# Robotics_Cape.net
KiCad netlist of a schematic drawn in EAGLE
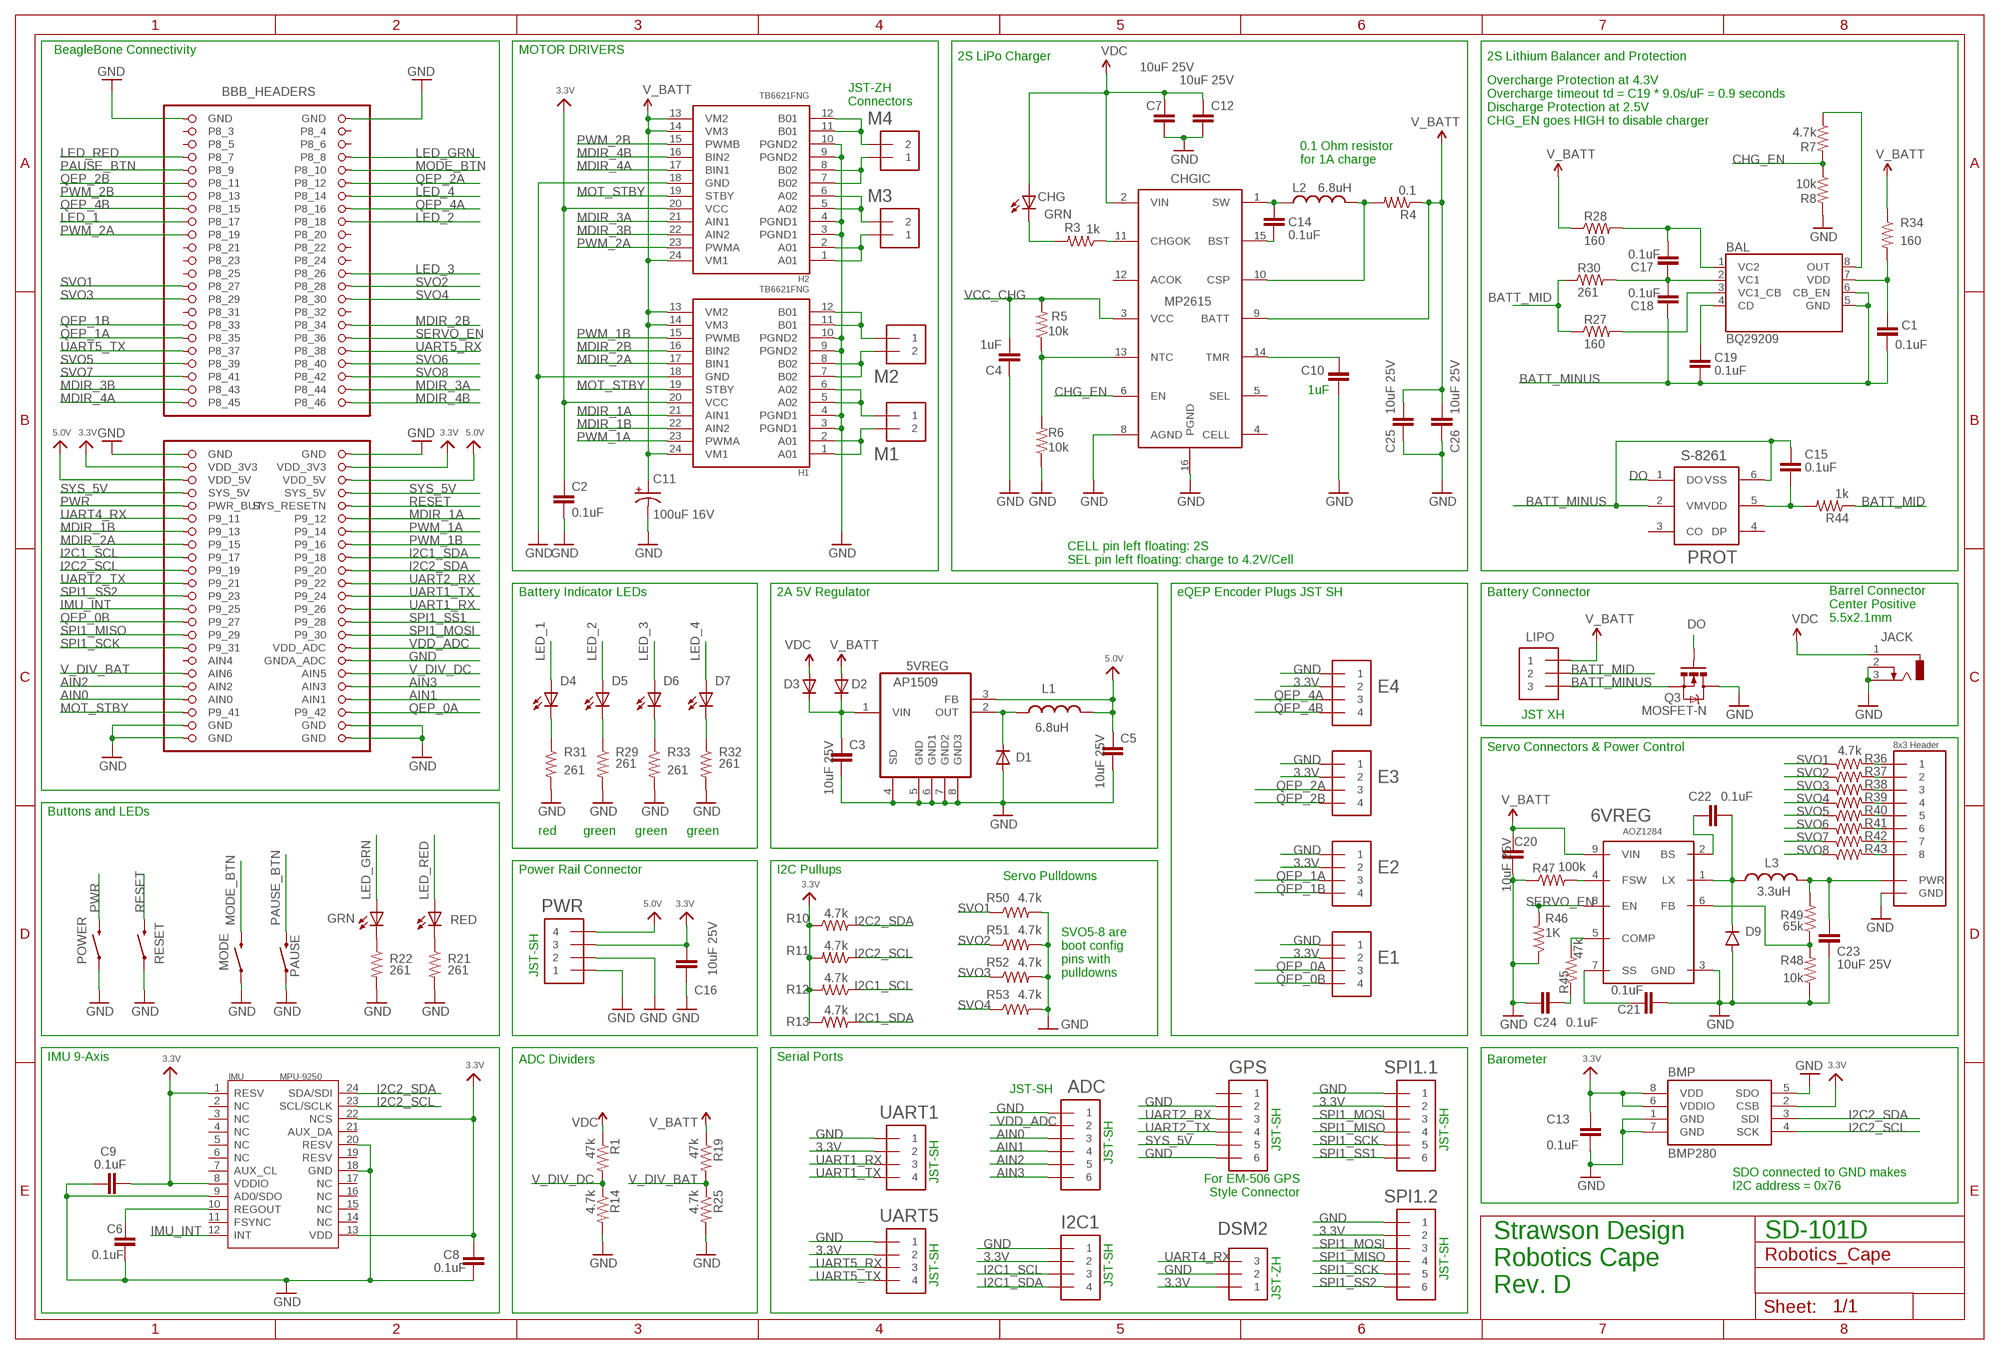
[diagram p0: schematic, sheet 1]

(export (version "E")
  (design (tool "Eeschema 10.0.6"))
  (components
    (comp (ref "5VREG")
      (value "AP1509SOIC-8-TIGHT")
      (footprint "eagle-import:SO08-TIGHT")
      (libsource (lib "eagle-import") (part "AP1509SOIC-8-TIGHT"))
    )
    (comp (ref "6VREG")
      (value "AOZ1284")
      (footprint "eagle-import:SO08-EXPOSED")
      (libsource (lib "eagle-import") (part "AOZ1284"))
    )
    (comp (ref "ADC")
      (value "JST_SH_6")
      (footprint "eagle-import:JST_SH_6")
      (libsource (lib "eagle-import") (part "JST_SH_6"))
    )
    (comp (ref "BAL")
      (value "BQ29209")
      (footprint "eagle-import:8-SON_3X3MM")
      (libsource (lib "eagle-import") (part "BQ29209"))
    )
    (comp (ref "BBB_HEADERS")
      (value "BEAGLEBONE_OUTLINE")
      (footprint "eagle-import:BEAGLEBONE_SHIELD")
      (libsource (lib "eagle-import") (part "BEAGLEBONE_OUTLINE"))
    )
    (comp (ref "BMP")
      (value "BMP280")
      (footprint "eagle-import:BMP280")
      (libsource (lib "eagle-import") (part "BMP280"))
    )
    (comp (ref "C1")
      (value "0.1uF")
      (footprint "eagle-import:0402-CAP")
      (libsource (lib "eagle-import") (part "Strawson_Eagle_Lib_CAP0402-CAP"))
    )
    (comp (ref "C2")
      (value "0.1uF")
      (footprint "eagle-import:0402-CAP")
      (libsource (lib "eagle-import") (part "Strawson_Eagle_Lib_CAP0402-CAP"))
    )
    (comp (ref "C3")
      (value "10uF 25V")
      (footprint "eagle-import:0805")
      (libsource (lib "eagle-import") (part "CAP0805"))
    )
    (comp (ref "C4")
      (value "1uF")
      (footprint "eagle-import:0402-CAP")
      (libsource (lib "eagle-import") (part "Strawson_Eagle_Lib_CAP0402-CAP"))
    )
    (comp (ref "C5")
      (value "10uF 25V")
      (footprint "eagle-import:0805")
      (libsource (lib "eagle-import") (part "CAP0805"))
    )
    (comp (ref "C6")
      (value "0.1uF")
      (footprint "eagle-import:0402-CAP")
      (libsource (lib "eagle-import") (part "Strawson_Eagle_Lib_CAP0402-CAP"))
    )
    (comp (ref "C7")
      (value "10uF 25V")
      (footprint "eagle-import:0805")
      (libsource (lib "eagle-import") (part "CAP0805"))
    )
    (comp (ref "C8")
      (value "0.1uF")
      (footprint "eagle-import:0402-CAP")
      (libsource (lib "eagle-import") (part "Strawson_Eagle_Lib_CAP0402-CAP"))
    )
    (comp (ref "C9")
      (value "0.1uF")
      (footprint "eagle-import:0402-CAP")
      (libsource (lib "eagle-import") (part "Strawson_Eagle_Lib_CAP0402-CAP"))
    )
    (comp (ref "C10")
      (value "1uF")
      (footprint "eagle-import:0402-CAP")
      (libsource (lib "eagle-import") (part "Strawson_Eagle_Lib_CAP0402-CAP"))
    )
    (comp (ref "C11")
      (value "100uF 16V")
      (footprint "eagle-import:PANASONIC_D")
      (libsource (lib "eagle-import") (part "CPOL-USD"))
    )
    (comp (ref "C12")
      (value "10uF 25V")
      (footprint "eagle-import:0805")
      (libsource (lib "eagle-import") (part "CAP0805"))
    )
    (comp (ref "C13")
      (value "0.1uF")
      (footprint "eagle-import:0402-CAP")
      (libsource (lib "eagle-import") (part "Strawson_Eagle_Lib_CAP0402-CAP"))
    )
    (comp (ref "C14")
      (value "0.1uF")
      (footprint "eagle-import:0402-CAP")
      (libsource (lib "eagle-import") (part "Strawson_Eagle_Lib_CAP0402-CAP"))
    )
    (comp (ref "C15")
      (value "0.1uF")
      (footprint "eagle-import:0402-CAP")
      (libsource (lib "eagle-import") (part "Strawson_Eagle_Lib_CAP0402-CAP"))
    )
    (comp (ref "C16")
      (value "10uF 25V")
      (footprint "eagle-import:0805")
      (libsource (lib "eagle-import") (part "CAP0805"))
    )
    (comp (ref "C17")
      (value "0.1uF")
      (footprint "eagle-import:0402-CAP")
      (libsource (lib "eagle-import") (part "Strawson_Eagle_Lib_CAP0402-CAP"))
    )
    (comp (ref "C18")
      (value "0.1uF")
      (footprint "eagle-import:0402-CAP")
      (libsource (lib "eagle-import") (part "Strawson_Eagle_Lib_CAP0402-CAP"))
    )
    (comp (ref "C19")
      (value "0.1uF")
      (footprint "eagle-import:0402-CAP")
      (libsource (lib "eagle-import") (part "Strawson_Eagle_Lib_CAP0402-CAP"))
    )
    (comp (ref "C20")
      (value "10uF 25V")
      (footprint "eagle-import:0805")
      (libsource (lib "eagle-import") (part "CAP0805"))
    )
    (comp (ref "C21")
      (value "0.1uF")
      (footprint "eagle-import:0402-CAP")
      (libsource (lib "eagle-import") (part "Strawson_Eagle_Lib_CAP0402-CAP"))
    )
    (comp (ref "C22")
      (value "0.1uF")
      (footprint "eagle-import:0402-CAP")
      (libsource (lib "eagle-import") (part "Strawson_Eagle_Lib_CAP0402-CAP"))
    )
    (comp (ref "C23")
      (value "10uF 25V")
      (footprint "eagle-import:0805")
      (libsource (lib "eagle-import") (part "CAP0805"))
    )
    (comp (ref "C24")
      (value "0.1uF")
      (footprint "eagle-import:0402-CAP")
      (libsource (lib "eagle-import") (part "Strawson_Eagle_Lib_CAP0402-CAP"))
    )
    (comp (ref "C25")
      (value "10uF 25V")
      (footprint "eagle-import:0805")
      (libsource (lib "eagle-import") (part "CAP0805"))
    )
    (comp (ref "C26")
      (value "10uF 25V")
      (footprint "eagle-import:0805")
      (libsource (lib "eagle-import") (part "CAP0805"))
    )
    (comp (ref "CHG")
      (value "GRN")
      (footprint "eagle-import:LED-0603")
      (libsource (lib "eagle-import") (part "LED0603"))
    )
    (comp (ref "CHGIC")
      (value "MP2615")
      (footprint "eagle-import:MP2615")
      (libsource (lib "eagle-import") (part "MP2615"))
    )
    (comp (ref "D1")
      (value "DIODESOD-123")
      (footprint "eagle-import:SOD-123")
      (libsource (lib "eagle-import") (part "DIODESOD-123"))
    )
    (comp (ref "D2")
      (value "DIODESOD-123")
      (footprint "eagle-import:SOD-123")
      (libsource (lib "eagle-import") (part "DIODESOD-123"))
    )
    (comp (ref "D3")
      (value "DIODESOD-123")
      (footprint "eagle-import:SOD-123")
      (libsource (lib "eagle-import") (part "DIODESOD-123"))
    )
    (comp (ref "D4")
      (value "RED")
      (footprint "eagle-import:LED-0603")
      (libsource (lib "eagle-import") (part "LED0603"))
    )
    (comp (ref "D5")
      (value "GREEN")
      (footprint "eagle-import:LED-0603")
      (libsource (lib "eagle-import") (part "LED0603"))
    )
    (comp (ref "D6")
      (value "GREEN")
      (footprint "eagle-import:LED-0603")
      (libsource (lib "eagle-import") (part "LED0603"))
    )
    (comp (ref "D7")
      (value "GREEN")
      (footprint "eagle-import:LED-0603")
      (libsource (lib "eagle-import") (part "LED0603"))
    )
    (comp (ref "D9")
      (value "DIODEDO214AA")
      (footprint "eagle-import:DO-214AA")
      (libsource (lib "eagle-import") (part "DIODEDO214AA"))
    )
    (comp (ref "DSM2")
      (value "JST_ZH_3")
      (footprint "eagle-import:JST_ZH_3")
      (libsource (lib "eagle-import") (part "JST_ZH_3"))
    )
    (comp (ref "E1")
      (value "JST_SH_4")
      (footprint "eagle-import:JST_SH_4_SMD")
      (libsource (lib "eagle-import") (part "JST_SH_4"))
    )
    (comp (ref "E2")
      (value "JST_SH_4")
      (footprint "eagle-import:JST_SH_4_SMD")
      (libsource (lib "eagle-import") (part "JST_SH_4"))
    )
    (comp (ref "E3")
      (value "JST_SH_4")
      (footprint "eagle-import:JST_SH_4_SMD")
      (libsource (lib "eagle-import") (part "JST_SH_4"))
    )
    (comp (ref "E4")
      (value "JST_SH_4")
      (footprint "eagle-import:JST_SH_4_SMD")
      (libsource (lib "eagle-import") (part "JST_SH_4"))
    )
    (comp (ref "GPS")
      (value "JST_SH_6")
      (footprint "eagle-import:JST_SH_6")
      (libsource (lib "eagle-import") (part "JST_SH_6"))
    )
    (comp (ref "GRN")
      (value "GRN")
      (footprint "eagle-import:LED-0603")
      (libsource (lib "eagle-import") (part "LED0603"))
    )
    (comp (ref "H1")
      (value "TB6621FNG")
      (footprint "eagle-import:SSOP24")
      (libsource (lib "eagle-import") (part "TB6621FNG"))
    )
    (comp (ref "H2")
      (value "TB6621FNG")
      (footprint "eagle-import:SSOP24")
      (libsource (lib "eagle-import") (part "TB6621FNG"))
    )
    (comp (ref "I2C1")
      (value "JST_SH_4")
      (footprint "eagle-import:JST_SH_4_SMD")
      (libsource (lib "eagle-import") (part "JST_SH_4"))
    )
    (comp (ref "IMU")
      (value "MPU-9250")
      (footprint "eagle-import:QFN24G-0.4-3X3MM")
      (libsource (lib "eagle-import") (part "MPU-9250"))
    )
    (comp (ref "JACK")
      (value "5.5x2.1mm")
      (footprint "eagle-import:DCJ0303")
      (libsource (lib "eagle-import") (part "DCJ0303"))
    )
    (comp (ref "L1")
      (value "6.8uH")
      (footprint "eagle-import:TAIYO_NRS")
      (libsource (lib "eagle-import") (part "INDUCTORTAIYO_NR-S"))
    )
    (comp (ref "L2")
      (value "6.8uH")
      (footprint "eagle-import:TAIYO_NRS")
      (libsource (lib "eagle-import") (part "INDUCTORTAIYO_NR-S"))
    )
    (comp (ref "L3")
      (value "3.3uH")
      (footprint "eagle-import:8X8MM_INDUCTOR")
      (libsource (lib "eagle-import") (part "INDUCTOR"))
    )
    (comp (ref "LIPO")
      (value "JST_XH_3-PIN")
      (footprint "eagle-import:JST_XH_3-PIN")
      (libsource (lib "eagle-import") (part "JST_XH_3-PIN"))
    )
    (comp (ref "M1")
      (value "JST_ZH_2")
      (footprint "eagle-import:JST_ZH_2")
      (libsource (lib "eagle-import") (part "JST_ZH_2"))
    )
    (comp (ref "M2")
      (value "JST_ZH_2")
      (footprint "eagle-import:JST_ZH_2")
      (libsource (lib "eagle-import") (part "JST_ZH_2"))
    )
    (comp (ref "M3")
      (value "JST_ZH_2")
      (footprint "eagle-import:JST_ZH_2")
      (libsource (lib "eagle-import") (part "JST_ZH_2"))
    )
    (comp (ref "M4")
      (value "JST_ZH_2")
      (footprint "eagle-import:JST_ZH_2")
      (libsource (lib "eagle-import") (part "JST_ZH_2"))
    )
    (comp (ref "MODE")
      (value "SWITCH-MOMENTARY-2-SMD-1101NE")
      (footprint "eagle-import:TACTILE-SWITCH-1101NE")
      (libsource (lib "eagle-import") (part "SWITCH-MOMENTARY-2-SMD-1101NE"))
    )
    (comp (ref "PAUSE")
      (value "SWITCH-MOMENTARY-2-SMD-1101NE")
      (footprint "eagle-import:TACTILE-SWITCH-1101NE")
      (libsource (lib "eagle-import") (part "SWITCH-MOMENTARY-2-SMD-1101NE"))
    )
    (comp (ref "POWER")
      (value "SWITCH-MOMENTARY-2-SMD-1101NE")
      (footprint "eagle-import:TACTILE-SWITCH-1101NE")
      (libsource (lib "eagle-import") (part "SWITCH-MOMENTARY-2-SMD-1101NE"))
    )
    (comp (ref "PROT")
      (value "S-8261")
      (footprint "eagle-import:SOT-236")
      (libsource (lib "eagle-import") (part "S-8261"))
    )
    (comp (ref "PWR")
      (value "JST_SH_4")
      (footprint "eagle-import:JST_SH_4_SMD")
      (libsource (lib "eagle-import") (part "JST_SH_4"))
    )
    (comp (ref "Q3")
      (value "MOSFET-N")
      (footprint "eagle-import:SO08-TIGHT")
      (libsource (lib "eagle-import") (part "MOSFET-NCHANNEL"))
    )
    (comp (ref "R1")
      (value "47k")
      (footprint "eagle-import:0402-RES")
      (libsource (lib "eagle-import") (part "RESISTOR0402-RES"))
    )
    (comp (ref "R3")
      (value "1k")
      (footprint "eagle-import:0402-RES")
      (libsource (lib "eagle-import") (part "RESISTOR0402-RES"))
    )
    (comp (ref "R4")
      (value "0.1")
      (footprint "eagle-import:0603-RES")
      (libsource (lib "eagle-import") (part "RESISTOR0603"))
    )
    (comp (ref "R5")
      (value "10k")
      (footprint "eagle-import:0402-RES")
      (libsource (lib "eagle-import") (part "RESISTOR0402-RES"))
    )
    (comp (ref "R6")
      (value "10k")
      (footprint "eagle-import:0402-RES")
      (libsource (lib "eagle-import") (part "RESISTOR0402-RES"))
    )
    (comp (ref "R7")
      (value "4.7k")
      (footprint "eagle-import:0402-RES")
      (libsource (lib "eagle-import") (part "RESISTOR0402-RES"))
    )
    (comp (ref "R8")
      (value "10k")
      (footprint "eagle-import:0402-RES")
      (libsource (lib "eagle-import") (part "RESISTOR0402-RES"))
    )
    (comp (ref "R10")
      (value "4.7k")
      (footprint "eagle-import:0402-RES")
      (libsource (lib "eagle-import") (part "RESISTOR0402-RES"))
    )
    (comp (ref "R11")
      (value "4.7k")
      (footprint "eagle-import:0402-RES")
      (libsource (lib "eagle-import") (part "RESISTOR0402-RES"))
    )
    (comp (ref "R12")
      (value "4.7k")
      (footprint "eagle-import:0402-RES")
      (libsource (lib "eagle-import") (part "RESISTOR0402-RES"))
    )
    (comp (ref "R13")
      (value "4.7k")
      (footprint "eagle-import:0402-RES")
      (libsource (lib "eagle-import") (part "RESISTOR0402-RES"))
    )
    (comp (ref "R14")
      (value "4.7k")
      (footprint "eagle-import:0402-RES")
      (libsource (lib "eagle-import") (part "RESISTOR0402-RES"))
    )
    (comp (ref "R19")
      (value "47k")
      (footprint "eagle-import:0402-RES")
      (libsource (lib "eagle-import") (part "RESISTOR0402-RES"))
    )
    (comp (ref "R21")
      (value "261")
      (footprint "eagle-import:0402-RES")
      (libsource (lib "eagle-import") (part "RESISTOR0402-RES"))
    )
    (comp (ref "R22")
      (value "261")
      (footprint "eagle-import:0402-RES")
      (libsource (lib "eagle-import") (part "RESISTOR0402-RES"))
    )
    (comp (ref "R25")
      (value "4.7k")
      (footprint "eagle-import:0402-RES")
      (libsource (lib "eagle-import") (part "RESISTOR0402-RES"))
    )
    (comp (ref "R27")
      (value "160")
      (footprint "eagle-import:0402-RES")
      (libsource (lib "eagle-import") (part "RESISTOR0402-RES"))
    )
    (comp (ref "R28")
      (value "160")
      (footprint "eagle-import:0402-RES")
      (libsource (lib "eagle-import") (part "RESISTOR0402-RES"))
    )
    (comp (ref "R29")
      (value "261")
      (footprint "eagle-import:0402-RES")
      (libsource (lib "eagle-import") (part "RESISTOR0402-RES"))
    )
    (comp (ref "R30")
      (value "261")
      (footprint "eagle-import:0402-RES")
      (libsource (lib "eagle-import") (part "RESISTOR0402-RES"))
    )
    (comp (ref "R31")
      (value "261")
      (footprint "eagle-import:0402-RES")
      (libsource (lib "eagle-import") (part "RESISTOR0402-RES"))
    )
    (comp (ref "R32")
      (value "261")
      (footprint "eagle-import:0402-RES")
      (libsource (lib "eagle-import") (part "RESISTOR0402-RES"))
    )
    (comp (ref "R33")
      (value "261")
      (footprint "eagle-import:0402-RES")
      (libsource (lib "eagle-import") (part "RESISTOR0402-RES"))
    )
    (comp (ref "R34")
      (value "160")
      (footprint "eagle-import:0402-RES")
      (libsource (lib "eagle-import") (part "RESISTOR0402-RES"))
    )
    (comp (ref "R36")
      (value "4.7k")
      (footprint "eagle-import:0402-RES")
      (libsource (lib "eagle-import") (part "RESISTOR0402-RES"))
    )
    (comp (ref "R37")
      (value "4.7k")
      (footprint "eagle-import:0402-RES")
      (libsource (lib "eagle-import") (part "RESISTOR0402-RES"))
    )
    (comp (ref "R38")
      (value "4.7k")
      (footprint "eagle-import:0402-RES")
      (libsource (lib "eagle-import") (part "RESISTOR0402-RES"))
    )
    (comp (ref "R39")
      (value "4.7k")
      (footprint "eagle-import:0402-RES")
      (libsource (lib "eagle-import") (part "RESISTOR0402-RES"))
    )
    (comp (ref "R40")
      (value "4.7k")
      (footprint "eagle-import:0402-RES")
      (libsource (lib "eagle-import") (part "RESISTOR0402-RES"))
    )
    (comp (ref "R41")
      (value "4.7k")
      (footprint "eagle-import:0402-RES")
      (libsource (lib "eagle-import") (part "RESISTOR0402-RES"))
    )
    (comp (ref "R42")
      (value "4.7k")
      (footprint "eagle-import:0402-RES")
      (libsource (lib "eagle-import") (part "RESISTOR0402-RES"))
    )
    (comp (ref "R43")
      (value "4.7k")
      (footprint "eagle-import:0402-RES")
      (libsource (lib "eagle-import") (part "RESISTOR0402-RES"))
    )
    (comp (ref "R44")
      (value "1k")
      (footprint "eagle-import:0402-RES")
      (libsource (lib "eagle-import") (part "RESISTOR0402-RES"))
    )
    (comp (ref "R45")
      (value "47k")
      (footprint "eagle-import:0402-RES")
      (libsource (lib "eagle-import") (part "RESISTOR0402-RES"))
    )
    (comp (ref "R46")
      (value "1K")
      (footprint "eagle-import:0402-RES")
      (libsource (lib "eagle-import") (part "RESISTOR0402-RES"))
    )
    (comp (ref "R47")
      (value "100k")
      (footprint "eagle-import:0402-RES")
      (libsource (lib "eagle-import") (part "RESISTOR0402-RES"))
    )
    (comp (ref "R48")
      (value "10k")
      (footprint "eagle-import:0402-RES")
      (libsource (lib "eagle-import") (part "RESISTOR0402-RES"))
    )
    (comp (ref "R49")
      (value "65k")
      (footprint "eagle-import:0402-RES")
      (libsource (lib "eagle-import") (part "RESISTOR0402-RES"))
    )
    (comp (ref "R50")
      (value "4.7k")
      (footprint "eagle-import:0402-RES")
      (libsource (lib "eagle-import") (part "RESISTOR0402-RES"))
    )
    (comp (ref "R51")
      (value "4.7k")
      (footprint "eagle-import:0402-RES")
      (libsource (lib "eagle-import") (part "RESISTOR0402-RES"))
    )
    (comp (ref "R52")
      (value "4.7k")
      (footprint "eagle-import:0402-RES")
      (libsource (lib "eagle-import") (part "RESISTOR0402-RES"))
    )
    (comp (ref "R53")
      (value "4.7k")
      (footprint "eagle-import:0402-RES")
      (libsource (lib "eagle-import") (part "RESISTOR0402-RES"))
    )
    (comp (ref "RED")
      (value "RED")
      (footprint "eagle-import:LED-0603")
      (libsource (lib "eagle-import") (part "LED0603"))
    )
    (comp (ref "RESET")
      (value "SWITCH-MOMENTARY-2-SMD-1101NE")
      (footprint "eagle-import:TACTILE-SWITCH-1101NE")
      (libsource (lib "eagle-import") (part "SWITCH-MOMENTARY-2-SMD-1101NE"))
    )
    (comp (ref "SPI1.1")
      (value "JST_SH_6")
      (footprint "eagle-import:JST_SH_6")
      (libsource (lib "eagle-import") (part "JST_SH_6"))
    )
    (comp (ref "SPI1.2")
      (value "JST_SH_6")
      (footprint "eagle-import:JST_SH_6")
      (libsource (lib "eagle-import") (part "JST_SH_6"))
    )
    (comp (ref "U$1")
      (value "SERVO_HEADERS_8X")
      (footprint "eagle-import:3X8_0.1__HEADER")
      (libsource (lib "eagle-import") (part "SERVO_HEADERS_8X"))
    )
    (comp (ref "UART1")
      (value "JST_SH_4")
      (footprint "eagle-import:JST_SH_4_SMD")
      (libsource (lib "eagle-import") (part "JST_SH_4"))
    )
    (comp (ref "UART5")
      (value "JST_SH_4")
      (footprint "eagle-import:JST_SH_4_SMD")
      (libsource (lib "eagle-import") (part "JST_SH_4"))
    )
  )
  (nets
    (net (code "1") (name "/AIN0") (class "Default")
      (node (ref "ADC") (pin "3") (pinfunction "3_3") (pintype "bidirectional"))
      (node (ref "BBB_HEADERS") (pin "85") (pinfunction "AIN0_85") (pintype "power_in"))
    )
    (net (code "2") (name "/AIN1") (class "Default")
      (node (ref "ADC") (pin "4") (pinfunction "4_4") (pintype "bidirectional"))
      (node (ref "BBB_HEADERS") (pin "86") (pinfunction "AIN1_86") (pintype "passive"))
    )
    (net (code "3") (name "/AIN2") (class "Default")
      (node (ref "ADC") (pin "5") (pinfunction "5_5") (pintype "bidirectional"))
      (node (ref "BBB_HEADERS") (pin "83") (pinfunction "AIN2_83") (pintype "passive"))
    )
    (net (code "4") (name "/AIN3") (class "Default")
      (node (ref "ADC") (pin "6") (pinfunction "6_6") (pintype "bidirectional"))
      (node (ref "BBB_HEADERS") (pin "84") (pinfunction "AIN3_84") (pintype "passive"))
    )
    (net (code "5") (name "/BATT_MID") (class "Default")
      (node (ref "LIPO") (pin "P$2") (pinfunction "2_P$2") (pintype "passive"))
      (node (ref "R27") (pin "1") (pinfunction "1_1") (pintype "passive"))
      (node (ref "R30") (pin "1") (pinfunction "1_1") (pintype "passive"))
      (node (ref "R44") (pin "1") (pinfunction "1_1") (pintype "passive"))
    )
    (net (code "6") (name "/BATT_MINUS") (class "Default")
      (node (ref "BAL") (pin "5") (pinfunction "GND_5") (pintype "bidirectional"))
      (node (ref "BAL") (pin "6") (pinfunction "CB_EN_6") (pintype "bidirectional"))
      (node (ref "C1") (pin "2") (pinfunction "2_2") (pintype "passive"))
      (node (ref "C15") (pin "1") (pinfunction "1_1") (pintype "passive"))
      (node (ref "C18") (pin "1") (pinfunction "1_1") (pintype "passive"))
      (node (ref "C19") (pin "2") (pinfunction "2_2") (pintype "passive"))
      (node (ref "LIPO") (pin "P$3") (pinfunction "3_P$3") (pintype "passive"))
      (node (ref "PROT") (pin "2") (pinfunction "VM_2") (pintype "bidirectional"))
      (node (ref "PROT") (pin "6") (pinfunction "VSS_6") (pintype "bidirectional"))
      (node (ref "Q3") (pin "1") (pinfunction "S_1") (pintype "passive"))
      (node (ref "Q3") (pin "2") (pinfunction "S_2") (pintype "passive"))
      (node (ref "Q3") (pin "3") (pinfunction "S_3") (pintype "passive"))
    )
    (net (code "7") (name "/CHG_EN") (class "Default")
      (node (ref "CHGIC") (pin "6") (pinfunction "EN_6") (pintype "bidirectional"))
      (node (ref "R7") (pin "2") (pinfunction "2_2") (pintype "passive"))
      (node (ref "R8") (pin "1") (pinfunction "1_1") (pintype "passive"))
    )
    (net (code "8") (name "/DO") (class "Default")
      (node (ref "PROT") (pin "1") (pinfunction "DO_1") (pintype "bidirectional"))
      (node (ref "Q3") (pin "4") (pinfunction "G_4") (pintype "passive"))
    )
    (net (code "9") (name "/I2C1_SCL") (class "Default")
      (node (ref "BBB_HEADERS") (pin "63") (pinfunction "P9_17_63") (pintype "passive"))
      (node (ref "I2C1") (pin "3") (pinfunction "3_3") (pintype "bidirectional"))
      (node (ref "R12") (pin "1") (pinfunction "1_1") (pintype "passive"))
    )
    (net (code "10") (name "/I2C1_SDA") (class "Default")
      (node (ref "BBB_HEADERS") (pin "64") (pinfunction "P9_18_64") (pintype "passive"))
      (node (ref "I2C1") (pin "4") (pinfunction "4_4") (pintype "bidirectional"))
      (node (ref "R13") (pin "2") (pinfunction "2_2") (pintype "passive"))
    )
    (net (code "11") (name "/I2C2_SCL") (class "Default")
      (node (ref "BBB_HEADERS") (pin "65") (pinfunction "P9_19_65") (pintype "passive"))
      (node (ref "BMP") (pin "4") (pinfunction "SCK_4") (pintype "input"))
      (node (ref "IMU") (pin "23") (pinfunction "SCL/SCLK_23") (pintype "bidirectional"))
      (node (ref "R11") (pin "1") (pinfunction "1_1") (pintype "passive"))
    )
    (net (code "12") (name "/I2C2_SDA") (class "Default")
      (node (ref "BBB_HEADERS") (pin "66") (pinfunction "P9_20_66") (pintype "passive"))
      (node (ref "BMP") (pin "3") (pinfunction "SDI_3") (pintype "bidirectional"))
      (node (ref "IMU") (pin "24") (pinfunction "SDA/SDI_24") (pintype "bidirectional"))
      (node (ref "R10") (pin "2") (pinfunction "2_2") (pintype "passive"))
    )
    (net (code "13") (name "/IMU_INT") (class "Default")
      (node (ref "BBB_HEADERS") (pin "71") (pinfunction "P9_25_71") (pintype "passive"))
      (node (ref "IMU") (pin "12") (pinfunction "INT_12") (pintype "bidirectional"))
    )
    (net (code "14") (name "/LED_1") (class "Default")
      (node (ref "BBB_HEADERS") (pin "17") (pinfunction "P8_17_17") (pintype "passive"))
      (node (ref "D4") (pin "A") (pinfunction "A_A") (pintype "passive"))
    )
    (net (code "15") (name "/LED_2") (class "Default")
      (node (ref "BBB_HEADERS") (pin "18") (pinfunction "P8_18_18") (pintype "passive"))
      (node (ref "D5") (pin "A") (pinfunction "A_A") (pintype "passive"))
    )
    (net (code "16") (name "/LED_3") (class "Default")
      (node (ref "BBB_HEADERS") (pin "26") (pinfunction "P8_26_26") (pintype "passive"))
      (node (ref "D6") (pin "A") (pinfunction "A_A") (pintype "passive"))
    )
    (net (code "17") (name "/LED_4") (class "Default")
      (node (ref "BBB_HEADERS") (pin "14") (pinfunction "P8_14_14") (pintype "passive"))
      (node (ref "D7") (pin "A") (pinfunction "A_A") (pintype "passive"))
    )
    (net (code "18") (name "/LED_GRN") (class "Default")
      (node (ref "BBB_HEADERS") (pin "8") (pinfunction "P8_8_8") (pintype "passive"))
      (node (ref "GRN") (pin "A") (pinfunction "A_A") (pintype "passive"))
    )
    (net (code "19") (name "/LED_RED") (class "Default")
      (node (ref "BBB_HEADERS") (pin "7") (pinfunction "P8_7_7") (pintype "passive"))
      (node (ref "RED") (pin "A") (pinfunction "A_A") (pintype "passive"))
    )
    (net (code "20") (name "/MDIR_1A") (class "Default")
      (node (ref "BBB_HEADERS") (pin "58") (pinfunction "P9_12_58") (pintype "passive"))
      (node (ref "H1") (pin "21") (pinfunction "AIN1_21") (pintype "bidirectional"))
    )
    (net (code "21") (name "/MDIR_1B") (class "Default")
      (node (ref "BBB_HEADERS") (pin "59") (pinfunction "P9_13_59") (pintype "passive"))
      (node (ref "H1") (pin "22") (pinfunction "AIN2_22") (pintype "bidirectional"))
    )
    (net (code "22") (name "/MDIR_2A") (class "Default")
      (node (ref "BBB_HEADERS") (pin "61") (pinfunction "P9_15_61") (pintype "passive"))
      (node (ref "H1") (pin "17") (pinfunction "BIN1_17") (pintype "bidirectional"))
    )
    (net (code "23") (name "/MDIR_2B") (class "Default")
      (node (ref "BBB_HEADERS") (pin "34") (pinfunction "P8_34_34") (pintype "passive"))
      (node (ref "H1") (pin "16") (pinfunction "BIN2_16") (pintype "bidirectional"))
    )
    (net (code "24") (name "/MDIR_3A") (class "Default")
      (node (ref "BBB_HEADERS") (pin "44") (pinfunction "P8_44_44") (pintype "passive"))
      (node (ref "H2") (pin "21") (pinfunction "AIN1_21") (pintype "bidirectional"))
    )
    (net (code "25") (name "/MDIR_3B") (class "Default")
      (node (ref "BBB_HEADERS") (pin "43") (pinfunction "P8_43_43") (pintype "passive"))
      (node (ref "H2") (pin "22") (pinfunction "AIN2_22") (pintype "bidirectional"))
    )
    (net (code "26") (name "/MDIR_4A") (class "Default")
      (node (ref "BBB_HEADERS") (pin "45") (pinfunction "P8_45_45") (pintype "passive"))
      (node (ref "H2") (pin "17") (pinfunction "BIN1_17") (pintype "bidirectional"))
    )
    (net (code "27") (name "/MDIR_4B") (class "Default")
      (node (ref "BBB_HEADERS") (pin "46") (pinfunction "P8_46_46") (pintype "passive"))
      (node (ref "H2") (pin "16") (pinfunction "BIN2_16") (pintype "bidirectional"))
    )
    (net (code "28") (name "/MODE_BTN") (class "Default")
      (node (ref "BBB_HEADERS") (pin "10") (pinfunction "P8_10_10") (pintype "passive"))
      (node (ref "MODE") (pin "P$2") (pinfunction "2_P$2") (pintype "passive"))
    )
    (net (code "29") (name "/MOT_STBY") (class "Default")
      (node (ref "BBB_HEADERS") (pin "87") (pinfunction "P9_41_87") (pintype "input"))
      (node (ref "H1") (pin "19") (pinfunction "STBY_19") (pintype "bidirectional"))
      (node (ref "H2") (pin "19") (pinfunction "STBY_19") (pintype "bidirectional"))
    )
    (net (code "30") (name "/PAUSE_BTN") (class "Default")
      (node (ref "BBB_HEADERS") (pin "9") (pinfunction "P8_9_9") (pintype "passive"))
      (node (ref "PAUSE") (pin "P$2") (pinfunction "2_P$2") (pintype "passive"))
    )
    (net (code "31") (name "/PWM_1A") (class "Default")
      (node (ref "BBB_HEADERS") (pin "60") (pinfunction "P9_14_60") (pintype "passive"))
      (node (ref "H1") (pin "23") (pinfunction "PWMA_23") (pintype "bidirectional"))
    )
    (net (code "32") (name "/PWM_1B") (class "Default")
      (node (ref "BBB_HEADERS") (pin "62") (pinfunction "P9_16_62") (pintype "passive"))
      (node (ref "H1") (pin "15") (pinfunction "PWMB_15") (pintype "bidirectional"))
    )
    (net (code "33") (name "/PWM_2A") (class "Default")
      (node (ref "BBB_HEADERS") (pin "19") (pinfunction "P8_19_19") (pintype "passive"))
      (node (ref "H2") (pin "23") (pinfunction "PWMA_23") (pintype "bidirectional"))
    )
    (net (code "34") (name "/PWM_2B") (class "Default")
      (node (ref "BBB_HEADERS") (pin "13") (pinfunction "P8_13_13") (pintype "passive"))
      (node (ref "H2") (pin "15") (pinfunction "PWMB_15") (pintype "bidirectional"))
    )
    (net (code "35") (name "/PWR") (class "Default")
      (node (ref "BBB_HEADERS") (pin "55") (pinfunction "PWR_BUT_55") (pintype "passive"))
      (node (ref "POWER") (pin "P$2") (pinfunction "2_P$2") (pintype "passive"))
    )
    (net (code "36") (name "/QEP_0A") (class "Default")
      (node (ref "BBB_HEADERS") (pin "88") (pinfunction "P9_42_88") (pintype "passive"))
      (node (ref "E1") (pin "3") (pinfunction "3_3") (pintype "bidirectional"))
    )
    (net (code "37") (name "/QEP_0B") (class "Default")
      (node (ref "BBB_HEADERS") (pin "73") (pinfunction "P9_27_73") (pintype "passive"))
      (node (ref "E1") (pin "4") (pinfunction "4_4") (pintype "bidirectional"))
    )
    (net (code "38") (name "/QEP_1A") (class "Default")
      (node (ref "BBB_HEADERS") (pin "35") (pinfunction "P8_35_35") (pintype "passive"))
      (node (ref "E2") (pin "3") (pinfunction "3_3") (pintype "bidirectional"))
    )
    (net (code "39") (name "/QEP_1B") (class "Default")
      (node (ref "BBB_HEADERS") (pin "33") (pinfunction "P8_33_33") (pintype "passive"))
      (node (ref "E2") (pin "4") (pinfunction "4_4") (pintype "bidirectional"))
    )
    (net (code "40") (name "/QEP_2A") (class "Default")
      (node (ref "BBB_HEADERS") (pin "12") (pinfunction "P8_12_12") (pintype "passive"))
      (node (ref "E3") (pin "3") (pinfunction "3_3") (pintype "bidirectional"))
    )
    (net (code "41") (name "/QEP_2B") (class "Default")
      (node (ref "BBB_HEADERS") (pin "11") (pinfunction "P8_11_11") (pintype "passive"))
      (node (ref "E3") (pin "4") (pinfunction "4_4") (pintype "bidirectional"))
    )
    (net (code "42") (name "/QEP_4A") (class "Default")
      (node (ref "BBB_HEADERS") (pin "16") (pinfunction "P8_16_16") (pintype "passive"))
      (node (ref "E4") (pin "3") (pinfunction "3_3") (pintype "bidirectional"))
    )
    (net (code "43") (name "/QEP_4B") (class "Default")
      (node (ref "BBB_HEADERS") (pin "15") (pinfunction "P8_15_15") (pintype "passive"))
      (node (ref "E4") (pin "4") (pinfunction "4_4") (pintype "bidirectional"))
    )
    (net (code "44") (name "/RESET") (class "Default")
      (node (ref "BBB_HEADERS") (pin "56") (pinfunction "SYS_RESETN_56") (pintype "passive"))
      (node (ref "RESET") (pin "P$2") (pinfunction "2_P$2") (pintype "passive"))
    )
    (net (code "45") (name "/SERVO_EN") (class "Default")
      (node (ref "6VREG") (pin "8") (pinfunction "EN_8") (pintype "bidirectional"))
      (node (ref "BBB_HEADERS") (pin "36") (pinfunction "P8_36_36") (pintype "passive"))
      (node (ref "R46") (pin "2") (pinfunction "2_2") (pintype "passive"))
    )
    (net (code "46") (name "/SPI1_MISO") (class "Default")
      (node (ref "BBB_HEADERS") (pin "75") (pinfunction "P9_29_75") (pintype "passive"))
      (node (ref "SPI1.1") (pin "4") (pinfunction "4_4") (pintype "bidirectional"))
      (node (ref "SPI1.2") (pin "4") (pinfunction "4_4") (pintype "bidirectional"))
    )
    (net (code "47") (name "/SPI1_MOSI") (class "Default")
      (node (ref "BBB_HEADERS") (pin "76") (pinfunction "P9_30_76") (pintype "passive"))
      (node (ref "SPI1.1") (pin "3") (pinfunction "3_3") (pintype "bidirectional"))
      (node (ref "SPI1.2") (pin "3") (pinfunction "3_3") (pintype "bidirectional"))
    )
    (net (code "48") (name "/SPI1_SCK") (class "Default")
      (node (ref "BBB_HEADERS") (pin "77") (pinfunction "P9_31_77") (pintype "passive"))
      (node (ref "SPI1.1") (pin "5") (pinfunction "5_5") (pintype "bidirectional"))
      (node (ref "SPI1.2") (pin "5") (pinfunction "5_5") (pintype "bidirectional"))
    )
    (net (code "49") (name "/SPI1_SS1") (class "Default")
      (node (ref "BBB_HEADERS") (pin "74") (pinfunction "P9_28_74") (pintype "passive"))
      (node (ref "SPI1.1") (pin "6") (pinfunction "6_6") (pintype "bidirectional"))
    )
    (net (code "50") (name "/SPI1_SS2") (class "Default")
      (node (ref "BBB_HEADERS") (pin "69") (pinfunction "P9_23_69") (pintype "passive"))
      (node (ref "SPI1.2") (pin "6") (pinfunction "6_6") (pintype "bidirectional"))
    )
    (net (code "51") (name "/SVO1") (class "Default")
      (node (ref "BBB_HEADERS") (pin "27") (pinfunction "P8_27_27") (pintype "passive"))
      (node (ref "R36") (pin "1") (pinfunction "1_1") (pintype "passive"))
      (node (ref "R50") (pin "1") (pinfunction "1_1") (pintype "passive"))
    )
    (net (code "52") (name "/SVO2") (class "Default")
      (node (ref "BBB_HEADERS") (pin "28") (pinfunction "P8_28_28") (pintype "passive"))
      (node (ref "R37") (pin "1") (pinfunction "1_1") (pintype "passive"))
      (node (ref "R51") (pin "1") (pinfunction "1_1") (pintype "passive"))
    )
    (net (code "53") (name "/SVO3") (class "Default")
      (node (ref "BBB_HEADERS") (pin "29") (pinfunction "P8_29_29") (pintype "passive"))
      (node (ref "R38") (pin "1") (pinfunction "1_1") (pintype "passive"))
      (node (ref "R52") (pin "1") (pinfunction "1_1") (pintype "passive"))
    )
    (net (code "54") (name "/SVO4") (class "Default")
      (node (ref "BBB_HEADERS") (pin "30") (pinfunction "P8_30_30") (pintype "passive"))
      (node (ref "R39") (pin "1") (pinfunction "1_1") (pintype "passive"))
      (node (ref "R53") (pin "1") (pinfunction "1_1") (pintype "passive"))
    )
    (net (code "55") (name "/SVO5") (class "Default")
      (node (ref "BBB_HEADERS") (pin "39") (pinfunction "P8_39_39") (pintype "passive"))
      (node (ref "R40") (pin "1") (pinfunction "1_1") (pintype "passive"))
    )
    (net (code "56") (name "/SVO6") (class "Default")
      (node (ref "BBB_HEADERS") (pin "40") (pinfunction "P8_40_40") (pintype "passive"))
      (node (ref "R41") (pin "1") (pinfunction "1_1") (pintype "passive"))
    )
    (net (code "57") (name "/SVO7") (class "Default")
      (node (ref "BBB_HEADERS") (pin "41") (pinfunction "P8_41_41") (pintype "passive"))
      (node (ref "R42") (pin "1") (pinfunction "1_1") (pintype "passive"))
    )
    (net (code "58") (name "/SVO8") (class "Default")
      (node (ref "BBB_HEADERS") (pin "42") (pinfunction "P8_42_42") (pintype "passive"))
      (node (ref "R43") (pin "1") (pinfunction "1_1") (pintype "passive"))
    )
    (net (code "59") (name "/SYS_5V") (class "Default")
      (node (ref "BBB_HEADERS") (pin "53") (pinfunction "SYS_5V_53") (pintype "power_in"))
      (node (ref "BBB_HEADERS") (pin "54") (pinfunction "SYS_5V_54") (pintype "passive"))
      (node (ref "GPS") (pin "5") (pinfunction "5_5") (pintype "bidirectional"))
    )
    (net (code "60") (name "/UART1_RX") (class "Default")
      (node (ref "BBB_HEADERS") (pin "72") (pinfunction "P9_26_72") (pintype "passive"))
      (node (ref "UART1") (pin "3") (pinfunction "3_3") (pintype "bidirectional"))
    )
    (net (code "61") (name "/UART1_TX") (class "Default")
      (node (ref "BBB_HEADERS") (pin "70") (pinfunction "P9_24_70") (pintype "passive"))
      (node (ref "UART1") (pin "4") (pinfunction "4_4") (pintype "bidirectional"))
    )
    (net (code "62") (name "/UART2_RX") (class "Default")
      (node (ref "BBB_HEADERS") (pin "68") (pinfunction "P9_22_68") (pintype "passive"))
      (node (ref "GPS") (pin "3") (pinfunction "3_3") (pintype "bidirectional"))
    )
    (net (code "63") (name "/UART2_TX") (class "Default")
      (node (ref "BBB_HEADERS") (pin "67") (pinfunction "P9_21_67") (pintype "passive"))
      (node (ref "GPS") (pin "4") (pinfunction "4_4") (pintype "bidirectional"))
    )
    (net (code "64") (name "/UART4_RX") (class "Default")
      (node (ref "BBB_HEADERS") (pin "57") (pinfunction "P9_11_57") (pintype "passive"))
      (node (ref "DSM2") (pin "P$3") (pinfunction "3_P$3") (pintype "bidirectional"))
    )
    (net (code "65") (name "/UART5_RX") (class "Default")
      (node (ref "BBB_HEADERS") (pin "38") (pinfunction "P8_38_38") (pintype "passive"))
      (node (ref "UART5") (pin "3") (pinfunction "3_3") (pintype "bidirectional"))
    )
    (net (code "66") (name "/UART5_TX") (class "Default")
      (node (ref "BBB_HEADERS") (pin "37") (pinfunction "P8_37_37") (pintype "passive"))
      (node (ref "UART5") (pin "4") (pinfunction "4_4") (pintype "bidirectional"))
    )
    (net (code "67") (name "/VCC_CHG") (class "Default")
      (node (ref "C4") (pin "2") (pinfunction "2_2") (pintype "passive"))
      (node (ref "CHGIC") (pin "3") (pinfunction "VCC_3") (pintype "bidirectional"))
      (node (ref "R5") (pin "2") (pinfunction "2_2") (pintype "passive"))
    )
    (net (code "68") (name "/VDD_ADC") (class "Default")
      (node (ref "ADC") (pin "2") (pinfunction "2_2") (pintype "bidirectional"))
      (node (ref "BBB_HEADERS") (pin "78") (pinfunction "VDD_ADC_78") (pintype "passive"))
    )
    (net (code "69") (name "/V_DIV_BAT") (class "Default")
      (node (ref "BBB_HEADERS") (pin "81") (pinfunction "AIN6_81") (pintype "passive"))
      (node (ref "R19") (pin "2") (pinfunction "2_2") (pintype "passive"))
      (node (ref "R25") (pin "1") (pinfunction "1_1") (pintype "passive"))
    )
    (net (code "70") (name "/V_DIV_DC") (class "Default")
      (node (ref "BBB_HEADERS") (pin "82") (pinfunction "AIN5_82") (pintype "passive"))
      (node (ref "R1") (pin "2") (pinfunction "2_2") (pintype "passive"))
      (node (ref "R14") (pin "1") (pinfunction "1_1") (pintype "passive"))
    )
    (net (code "71") (name "3.3V") (class "Default")
      (node (ref "BBB_HEADERS") (pin "49") (pinfunction "VDD_3V3_49") (pintype "power_in"))
      (node (ref "BBB_HEADERS") (pin "50") (pinfunction "VDD_3V3_50") (pintype "power_in"))
      (node (ref "BMP") (pin "2") (pinfunction "CSB_2") (pintype "input"))
      (node (ref "BMP") (pin "6") (pinfunction "VDDIO_6") (pintype "input"))
      (node (ref "BMP") (pin "8") (pinfunction "VDD_8") (pintype "power_in"))
      (node (ref "C13") (pin "1") (pinfunction "1_1") (pintype "passive"))
      (node (ref "C16") (pin "1") (pinfunction "1_1") (pintype "passive"))
      (node (ref "C2") (pin "2") (pinfunction "2_2") (pintype "passive"))
      (node (ref "C8") (pin "1") (pinfunction "1_1") (pintype "passive"))
      (node (ref "C9") (pin "2") (pinfunction "2_2") (pintype "passive"))
      (node (ref "DSM2") (pin "P$1") (pinfunction "1_P$1") (pintype "bidirectional"))
      (node (ref "E1") (pin "2") (pinfunction "2_2") (pintype "bidirectional"))
      (node (ref "E2") (pin "2") (pinfunction "2_2") (pintype "bidirectional"))
      (node (ref "E3") (pin "2") (pinfunction "2_2") (pintype "bidirectional"))
      (node (ref "E4") (pin "2") (pinfunction "2_2") (pintype "bidirectional"))
      (node (ref "H1") (pin "20") (pinfunction "VCC_20") (pintype "bidirectional"))
      (node (ref "H2") (pin "20") (pinfunction "VCC_20") (pintype "bidirectional"))
      (node (ref "I2C1") (pin "2") (pinfunction "2_2") (pintype "bidirectional"))
      (node (ref "IMU") (pin "1") (pinfunction "RESV_1") (pintype "bidirectional"))
      (node (ref "IMU") (pin "13") (pinfunction "VDD_13") (pintype "bidirectional"))
      (node (ref "IMU") (pin "22") (pinfunction "NCS_22") (pintype "bidirectional"))
      (node (ref "IMU") (pin "8") (pinfunction "VDDIO_8") (pintype "bidirectional"))
      (node (ref "PWR") (pin "3") (pinfunction "3_3") (pintype "bidirectional"))
      (node (ref "R10") (pin "1") (pinfunction "1_1") (pintype "passive"))
      (node (ref "R11") (pin "2") (pinfunction "2_2") (pintype "passive"))
      (node (ref "R12") (pin "2") (pinfunction "2_2") (pintype "passive"))
      (node (ref "R13") (pin "1") (pinfunction "1_1") (pintype "passive"))
      (node (ref "SPI1.1") (pin "2") (pinfunction "2_2") (pintype "bidirectional"))
      (node (ref "SPI1.2") (pin "2") (pinfunction "2_2") (pintype "bidirectional"))
      (node (ref "UART1") (pin "2") (pinfunction "2_2") (pintype "bidirectional"))
      (node (ref "UART5") (pin "2") (pinfunction "2_2") (pintype "bidirectional"))
    )
    (net (code "72") (name "5.0V") (class "Default")
      (node (ref "5VREG") (pin "3") (pinfunction "FB_3") (pintype "output"))
      (node (ref "BBB_HEADERS") (pin "51") (pinfunction "VDD_5V_51") (pintype "power_in"))
      (node (ref "BBB_HEADERS") (pin "52") (pinfunction "VDD_5V_52") (pintype "power_in"))
      (node (ref "C5") (pin "1") (pinfunction "1_1") (pintype "passive"))
      (node (ref "L1") (pin "2") (pinfunction "2_2") (pintype "passive"))
      (node (ref "PWR") (pin "4") (pinfunction "4_4") (pintype "bidirectional"))
    )
    (net (code "73") (name "GND") (class "Default")
      (node (ref "5VREG") (pin "4") (pinfunction "SD_4") (pintype "input"))
      (node (ref "5VREG") (pin "5") (pinfunction "GND_5") (pintype "power_in"))
      (node (ref "5VREG") (pin "6") (pinfunction "GND1_6") (pintype "input"))
      (node (ref "5VREG") (pin "7") (pinfunction "GND2_7") (pintype "passive"))
      (node (ref "5VREG") (pin "8") (pinfunction "GND3_8") (pintype "power_in"))
      (node (ref "6VREG") (pin "3") (pinfunction "GND_3") (pintype "bidirectional"))
      (node (ref "ADC") (pin "1") (pinfunction "1_1") (pintype "bidirectional"))
      (node (ref "BBB_HEADERS") (pin "1") (pinfunction "GND_1") (pintype "power_in"))
      (node (ref "BBB_HEADERS") (pin "2") (pinfunction "GND_2") (pintype "power_in"))
      (node (ref "BBB_HEADERS") (pin "47") (pinfunction "GND_47") (pintype "power_in"))
      (node (ref "BBB_HEADERS") (pin "48") (pinfunction "GND_48") (pintype "power_in"))
      (node (ref "BBB_HEADERS") (pin "80") (pinfunction "GNDA_ADC_80") (pintype "passive"))
      (node (ref "BBB_HEADERS") (pin "89") (pinfunction "GND_89") (pintype "power_in"))
      (node (ref "BBB_HEADERS") (pin "90") (pinfunction "GND_90") (pintype "power_in"))
      (node (ref "BBB_HEADERS") (pin "91") (pinfunction "GND_91") (pintype "power_in"))
      (node (ref "BBB_HEADERS") (pin "92") (pinfunction "GND_92") (pintype "power_in"))
      (node (ref "BMP") (pin "1") (pinfunction "GND_1") (pintype "power_in"))
      (node (ref "BMP") (pin "5") (pinfunction "SDO_5") (pintype "bidirectional"))
      (node (ref "BMP") (pin "7") (pinfunction "GND_7") (pintype "power_in"))
      (node (ref "C10") (pin "1") (pinfunction "1_1") (pintype "passive"))
      (node (ref "C11") (pin "-") (pinfunction "-_-") (pintype "passive"))
      (node (ref "C12") (pin "2") (pinfunction "2_2") (pintype "passive"))
      (node (ref "C13") (pin "2") (pinfunction "2_2") (pintype "passive"))
      (node (ref "C16") (pin "2") (pinfunction "2_2") (pintype "passive"))
      (node (ref "C2") (pin "1") (pinfunction "1_1") (pintype "passive"))
      (node (ref "C20") (pin "1") (pinfunction "1_1") (pintype "passive"))
      (node (ref "C21") (pin "1") (pinfunction "1_1") (pintype "passive"))
      (node (ref "C23") (pin "1") (pinfunction "1_1") (pintype "passive"))
      (node (ref "C24") (pin "1") (pinfunction "1_1") (pintype "passive"))
      (node (ref "C25") (pin "2") (pinfunction "2_2") (pintype "passive"))
      (node (ref "C26") (pin "2") (pinfunction "2_2") (pintype "passive"))
      (node (ref "C3") (pin "2") (pinfunction "2_2") (pintype "passive"))
      (node (ref "C4") (pin "1") (pinfunction "1_1") (pintype "passive"))
      (node (ref "C5") (pin "2") (pinfunction "2_2") (pintype "passive"))
      (node (ref "C6") (pin "2") (pinfunction "2_2") (pintype "passive"))
      (node (ref "C7") (pin "2") (pinfunction "2_2") (pintype "passive"))
      (node (ref "C8") (pin "2") (pinfunction "2_2") (pintype "passive"))
      (node (ref "C9") (pin "1") (pinfunction "1_1") (pintype "passive"))
      (node (ref "CHGIC") (pin "16") (pinfunction "PGND_16") (pintype "bidirectional"))
      (node (ref "CHGIC") (pin "8") (pinfunction "AGND_8") (pintype "bidirectional"))
      (node (ref "D1") (pin "A") (pinfunction "A_A") (pintype "passive"))
      (node (ref "D9") (pin "A") (pinfunction "A_A") (pintype "passive"))
      (node (ref "DSM2") (pin "P$2") (pinfunction "2_P$2") (pintype "bidirectional"))
      (node (ref "E1") (pin "1") (pinfunction "1_1") (pintype "bidirectional"))
      (node (ref "E2") (pin "1") (pinfunction "1_1") (pintype "bidirectional"))
      (node (ref "E3") (pin "1") (pinfunction "1_1") (pintype "bidirectional"))
      (node (ref "E4") (pin "1") (pinfunction "1_1") (pintype "bidirectional"))
      (node (ref "GPS") (pin "2") (pinfunction "2_2") (pintype "bidirectional"))
      (node (ref "GPS") (pin "6") (pinfunction "6_6") (pintype "bidirectional"))
      (node (ref "H1") (pin "10") (pinfunction "PGND2_10") (pintype "bidirectional"))
      (node (ref "H1") (pin "18") (pinfunction "GND_18") (pintype "bidirectional"))
      (node (ref "H1") (pin "3") (pinfunction "PGND1_3") (pintype "bidirectional"))
      (node (ref "H1") (pin "4") (pinfunction "PGND1_4") (pintype "bidirectional"))
      (node (ref "H1") (pin "9") (pinfunction "PGND2_9") (pintype "bidirectional"))
      (node (ref "H2") (pin "10") (pinfunction "PGND2_10") (pintype "bidirectional"))
      (node (ref "H2") (pin "18") (pinfunction "GND_18") (pintype "bidirectional"))
      (node (ref "H2") (pin "3") (pinfunction "PGND1_3") (pintype "bidirectional"))
      (node (ref "H2") (pin "4") (pinfunction "PGND1_4") (pintype "bidirectional"))
      (node (ref "H2") (pin "9") (pinfunction "PGND2_9") (pintype "bidirectional"))
      (node (ref "I2C1") (pin "1") (pinfunction "1_1") (pintype "bidirectional"))
      (node (ref "IMU") (pin "18") (pinfunction "GND_18") (pintype "bidirectional"))
      (node (ref "IMU") (pin "20") (pinfunction "RESV_20") (pintype "bidirectional"))
      (node (ref "IMU") (pin "9") (pinfunction "AD0/SDO_9") (pintype "bidirectional"))
      (node (ref "JACK") (pin "2") (pinfunction "2_2") (pintype "passive"))
      (node (ref "JACK") (pin "3") (pinfunction "3_3") (pintype "passive"))
      (node (ref "MODE") (pin "P$1") (pinfunction "1_P$1") (pintype "passive"))
      (node (ref "PAUSE") (pin "P$1") (pinfunction "1_P$1") (pintype "passive"))
      (node (ref "POWER") (pin "P$1") (pinfunction "1_P$1") (pintype "passive"))
      (node (ref "PWR") (pin "1") (pinfunction "1_1") (pintype "bidirectional"))
      (node (ref "PWR") (pin "2") (pinfunction "2_2") (pintype "bidirectional"))
      (node (ref "Q3") (pin "5") (pinfunction "D_5") (pintype "passive"))
      (node (ref "Q3") (pin "6") (pinfunction "D_6") (pintype "passive"))
      (node (ref "Q3") (pin "7") (pinfunction "D_7") (pintype "passive"))
      (node (ref "Q3") (pin "8") (pinfunction "D_8") (pintype "passive"))
      (node (ref "R14") (pin "2") (pinfunction "2_2") (pintype "passive"))
      (node (ref "R21") (pin "2") (pinfunction "2_2") (pintype "passive"))
      (node (ref "R22") (pin "2") (pinfunction "2_2") (pintype "passive"))
      (node (ref "R25") (pin "2") (pinfunction "2_2") (pintype "passive"))
      (node (ref "R29") (pin "2") (pinfunction "2_2") (pintype "passive"))
      (node (ref "R31") (pin "2") (pinfunction "2_2") (pintype "passive"))
      (node (ref "R32") (pin "2") (pinfunction "2_2") (pintype "passive"))
      (node (ref "R33") (pin "2") (pinfunction "2_2") (pintype "passive"))
      (node (ref "R46") (pin "1") (pinfunction "1_1") (pintype "passive"))
      (node (ref "R47") (pin "1") (pinfunction "1_1") (pintype "passive"))
      (node (ref "R48") (pin "1") (pinfunction "1_1") (pintype "passive"))
      (node (ref "R50") (pin "2") (pinfunction "2_2") (pintype "passive"))
      (node (ref "R51") (pin "2") (pinfunction "2_2") (pintype "passive"))
      (node (ref "R52") (pin "2") (pinfunction "2_2") (pintype "passive"))
      (node (ref "R53") (pin "2") (pinfunction "2_2") (pintype "passive"))
      (node (ref "R6") (pin "1") (pinfunction "1_1") (pintype "passive"))
      (node (ref "R8") (pin "2") (pinfunction "2_2") (pintype "passive"))
      (node (ref "RESET") (pin "P$1") (pinfunction "1_P$1") (pintype "passive"))
      (node (ref "SPI1.1") (pin "1") (pinfunction "1_1") (pintype "bidirectional"))
      (node (ref "SPI1.2") (pin "1") (pinfunction "1_1") (pintype "bidirectional"))
      (node (ref "U$1") (pin "P$13") (pinfunction "GND_P$13") (pintype "bidirectional"))
      (node (ref "U$1") (pin "P$14") (pinfunction "GND_P$14") (pintype "bidirectional"))
      (node (ref "U$1") (pin "P$15") (pinfunction "GND_P$15") (pintype "bidirectional"))
      (node (ref "U$1") (pin "P$16") (pinfunction "GND_P$16") (pintype "bidirectional"))
      (node (ref "U$1") (pin "P$17") (pinfunction "GND_P$17") (pintype "bidirectional"))
      (node (ref "U$1") (pin "P$18") (pinfunction "GND_P$18") (pintype "bidirectional"))
      (node (ref "U$1") (pin "P$23") (pinfunction "GND_P$23") (pintype "bidirectional"))
      (node (ref "U$1") (pin "P$24") (pinfunction "GND_P$24") (pintype "bidirectional"))
      (node (ref "UART1") (pin "1") (pinfunction "1_1") (pintype "bidirectional"))
      (node (ref "UART5") (pin "1") (pinfunction "1_1") (pintype "bidirectional"))
    )
    (net (code "74") (name "Net-(5VREG-OUT)") (class "Default")
      (node (ref "5VREG") (pin "2") (pinfunction "OUT_2") (pintype "output"))
      (node (ref "D1") (pin "C") (pinfunction "C_C") (pintype "passive"))
      (node (ref "L1") (pin "1") (pinfunction "1_1") (pintype "passive"))
    )
    (net (code "75") (name "Net-(5VREG-VIN)") (class "Default")
      (node (ref "5VREG") (pin "1") (pinfunction "VIN_1") (pintype "input"))
      (node (ref "C3") (pin "1") (pinfunction "1_1") (pintype "passive"))
      (node (ref "D2") (pin "C") (pinfunction "C_C") (pintype "passive"))
      (node (ref "D3") (pin "C") (pinfunction "C_C") (pintype "passive"))
    )
    (net (code "76") (name "Net-(6VREG-BS)") (class "Default")
      (node (ref "6VREG") (pin "2") (pinfunction "BS_2") (pintype "bidirectional"))
      (node (ref "C22") (pin "1") (pinfunction "1_1") (pintype "passive"))
    )
    (net (code "77") (name "Net-(6VREG-COMP)") (class "Default")
      (node (ref "6VREG") (pin "5") (pinfunction "COMP_5") (pintype "bidirectional"))
      (node (ref "R45") (pin "2") (pinfunction "2_2") (pintype "passive"))
    )
    (net (code "78") (name "Net-(6VREG-FB)") (class "Default")
      (node (ref "6VREG") (pin "6") (pinfunction "FB_6") (pintype "bidirectional"))
      (node (ref "R48") (pin "2") (pinfunction "2_2") (pintype "passive"))
      (node (ref "R49") (pin "1") (pinfunction "1_1") (pintype "passive"))
    )
    (net (code "79") (name "Net-(6VREG-FSW)") (class "Default")
      (node (ref "6VREG") (pin "4") (pinfunction "FSW_4") (pintype "bidirectional"))
      (node (ref "R47") (pin "2") (pinfunction "2_2") (pintype "passive"))
    )
    (net (code "80") (name "Net-(6VREG-LX)") (class "Default")
      (node (ref "6VREG") (pin "1") (pinfunction "LX_1") (pintype "bidirectional"))
      (node (ref "C22") (pin "2") (pinfunction "2_2") (pintype "passive"))
      (node (ref "D9") (pin "C") (pinfunction "C_C") (pintype "passive"))
      (node (ref "L3") (pin "1") (pinfunction "1_1") (pintype "passive"))
    )
    (net (code "81") (name "Net-(6VREG-SS)") (class "Default")
      (node (ref "6VREG") (pin "7") (pinfunction "SS_7") (pintype "bidirectional"))
      (node (ref "C21") (pin "2") (pinfunction "2_2") (pintype "passive"))
    )
    (net (code "82") (name "Net-(BAL-CD)") (class "Default")
      (node (ref "BAL") (pin "4") (pinfunction "CD_4") (pintype "bidirectional"))
      (node (ref "C19") (pin "1") (pinfunction "1_1") (pintype "passive"))
    )
    (net (code "83") (name "Net-(BAL-OUT)") (class "Default")
      (node (ref "BAL") (pin "8") (pinfunction "OUT_8") (pintype "bidirectional"))
      (node (ref "R7") (pin "1") (pinfunction "1_1") (pintype "passive"))
    )
    (net (code "84") (name "Net-(BAL-VC1)") (class "Default")
      (node (ref "BAL") (pin "2") (pinfunction "VC1_2") (pintype "bidirectional"))
      (node (ref "C17") (pin "1") (pinfunction "1_1") (pintype "passive"))
      (node (ref "C18") (pin "2") (pinfunction "2_2") (pintype "passive"))
      (node (ref "R30") (pin "2") (pinfunction "2_2") (pintype "passive"))
    )
    (net (code "85") (name "Net-(BAL-VC1_CB)") (class "Default")
      (node (ref "BAL") (pin "3") (pinfunction "VC1_CB_3") (pintype "bidirectional"))
      (node (ref "R27") (pin "2") (pinfunction "2_2") (pintype "passive"))
    )
    (net (code "86") (name "Net-(BAL-VC2)") (class "Default")
      (node (ref "BAL") (pin "1") (pinfunction "VC2_1") (pintype "bidirectional"))
      (node (ref "C17") (pin "2") (pinfunction "2_2") (pintype "passive"))
      (node (ref "R28") (pin "2") (pinfunction "2_2") (pintype "passive"))
    )
    (net (code "87") (name "Net-(BAL-VDD)") (class "Default")
      (node (ref "BAL") (pin "7") (pinfunction "VDD_7") (pintype "bidirectional"))
      (node (ref "C1") (pin "1") (pinfunction "1_1") (pintype "passive"))
      (node (ref "R34") (pin "2") (pinfunction "2_2") (pintype "passive"))
    )
    (net (code "88") (name "Net-(C23-Pad2)") (class "Default")
      (node (ref "C23") (pin "2") (pinfunction "2_2") (pintype "passive"))
      (node (ref "L3") (pin "2") (pinfunction "2_2") (pintype "passive"))
      (node (ref "R49") (pin "2") (pinfunction "2_2") (pintype "passive"))
      (node (ref "U$1") (pin "P$10") (pinfunction "PWR_P$10") (pintype "bidirectional"))
      (node (ref "U$1") (pin "P$11") (pinfunction "PWR_P$11") (pintype "bidirectional"))
      (node (ref "U$1") (pin "P$12") (pinfunction "PWR_P$12") (pintype "bidirectional"))
      (node (ref "U$1") (pin "P$21") (pinfunction "PWR_P$21") (pintype "bidirectional"))
      (node (ref "U$1") (pin "P$22") (pinfunction "PWR_P$22") (pintype "bidirectional"))
      (node (ref "U$1") (pin "P$7") (pinfunction "PWR_P$7") (pintype "bidirectional"))
      (node (ref "U$1") (pin "P$8") (pinfunction "PWR_P$8") (pintype "bidirectional"))
      (node (ref "U$1") (pin "P$9") (pinfunction "PWR_P$9") (pintype "bidirectional"))
    )
    (net (code "89") (name "Net-(C24-Pad2)") (class "Default")
      (node (ref "C24") (pin "2") (pinfunction "2_2") (pintype "passive"))
      (node (ref "R45") (pin "1") (pinfunction "1_1") (pintype "passive"))
    )
    (net (code "90") (name "Net-(CHG-PadC)") (class "Default")
      (node (ref "CHG") (pin "C") (pinfunction "C_C") (pintype "passive"))
      (node (ref "R3") (pin "2") (pinfunction "2_2") (pintype "passive"))
    )
    (net (code "91") (name "Net-(CHGIC-BST)") (class "Default")
      (node (ref "C14") (pin "1") (pinfunction "1_1") (pintype "passive"))
      (node (ref "CHGIC") (pin "15") (pinfunction "BST_15") (pintype "bidirectional"))
    )
    (net (code "92") (name "Net-(CHGIC-CHGOK)") (class "Default")
      (node (ref "CHGIC") (pin "11") (pinfunction "CHGOK_11") (pintype "bidirectional"))
      (node (ref "R3") (pin "1") (pinfunction "1_1") (pintype "passive"))
    )
    (net (code "93") (name "Net-(CHGIC-CSP)") (class "Default")
      (node (ref "CHGIC") (pin "10") (pinfunction "CSP_10") (pintype "bidirectional"))
      (node (ref "L2") (pin "2") (pinfunction "2_2") (pintype "passive"))
      (node (ref "R4") (pin "2") (pinfunction "2_2") (pintype "passive"))
    )
    (net (code "94") (name "Net-(CHGIC-NTC)") (class "Default")
      (node (ref "CHGIC") (pin "13") (pinfunction "NTC_13") (pintype "bidirectional"))
      (node (ref "R5") (pin "1") (pinfunction "1_1") (pintype "passive"))
      (node (ref "R6") (pin "2") (pinfunction "2_2") (pintype "passive"))
    )
    (net (code "95") (name "Net-(CHGIC-SW)") (class "Default")
      (node (ref "C14") (pin "2") (pinfunction "2_2") (pintype "passive"))
      (node (ref "CHGIC") (pin "1") (pinfunction "SW_1") (pintype "bidirectional"))
      (node (ref "L2") (pin "1") (pinfunction "1_1") (pintype "passive"))
    )
    (net (code "96") (name "Net-(CHGIC-TMR)") (class "Default")
      (node (ref "C10") (pin "2") (pinfunction "2_2") (pintype "passive"))
      (node (ref "CHGIC") (pin "14") (pinfunction "TMR_14") (pintype "bidirectional"))
    )
    (net (code "97") (name "Net-(D4-PadC)") (class "Default")
      (node (ref "D4") (pin "C") (pinfunction "C_C") (pintype "passive"))
      (node (ref "R31") (pin "1") (pinfunction "1_1") (pintype "passive"))
    )
    (net (code "98") (name "Net-(D5-PadC)") (class "Default")
      (node (ref "D5") (pin "C") (pinfunction "C_C") (pintype "passive"))
      (node (ref "R29") (pin "1") (pinfunction "1_1") (pintype "passive"))
    )
    (net (code "99") (name "Net-(D6-PadC)") (class "Default")
      (node (ref "D6") (pin "C") (pinfunction "C_C") (pintype "passive"))
      (node (ref "R33") (pin "1") (pinfunction "1_1") (pintype "passive"))
    )
    (net (code "100") (name "Net-(D7-PadC)") (class "Default")
      (node (ref "D7") (pin "C") (pinfunction "C_C") (pintype "passive"))
      (node (ref "R32") (pin "1") (pinfunction "1_1") (pintype "passive"))
    )
    (net (code "101") (name "Net-(GRN-PadC)") (class "Default")
      (node (ref "GRN") (pin "C") (pinfunction "C_C") (pintype "passive"))
      (node (ref "R22") (pin "1") (pinfunction "1_1") (pintype "passive"))
    )
    (net (code "102") (name "Net-(IMU-REGOUT)") (class "Default")
      (node (ref "C6") (pin "1") (pinfunction "1_1") (pintype "passive"))
      (node (ref "IMU") (pin "10") (pinfunction "REGOUT_10") (pintype "bidirectional"))
    )
    (net (code "103") (name "Net-(M1-1)") (class "Default")
      (node (ref "H1") (pin "5") (pinfunction "A02_5") (pintype "bidirectional"))
      (node (ref "H1") (pin "6") (pinfunction "A02_6") (pintype "bidirectional"))
      (node (ref "M1") (pin "P$1") (pinfunction "1_P$1") (pintype "bidirectional"))
    )
    (net (code "104") (name "Net-(M1-2)") (class "Default")
      (node (ref "H1") (pin "1") (pinfunction "A01_1") (pintype "bidirectional"))
      (node (ref "H1") (pin "2") (pinfunction "A01_2") (pintype "bidirectional"))
      (node (ref "M1") (pin "P$2") (pinfunction "2_P$2") (pintype "bidirectional"))
    )
    (net (code "105") (name "Net-(M2-1)") (class "Default")
      (node (ref "H1") (pin "11") (pinfunction "B01_11") (pintype "bidirectional"))
      (node (ref "H1") (pin "12") (pinfunction "B01_12") (pintype "bidirectional"))
      (node (ref "M2") (pin "P$1") (pinfunction "1_P$1") (pintype "bidirectional"))
    )
    (net (code "106") (name "Net-(M2-2)") (class "Default")
      (node (ref "H1") (pin "7") (pinfunction "B02_7") (pintype "bidirectional"))
      (node (ref "H1") (pin "8") (pinfunction "B02_8") (pintype "bidirectional"))
      (node (ref "M2") (pin "P$2") (pinfunction "2_P$2") (pintype "bidirectional"))
    )
    (net (code "107") (name "Net-(M3-1)") (class "Default")
      (node (ref "H2") (pin "1") (pinfunction "A01_1") (pintype "bidirectional"))
      (node (ref "H2") (pin "2") (pinfunction "A01_2") (pintype "bidirectional"))
      (node (ref "M3") (pin "P$1") (pinfunction "1_P$1") (pintype "bidirectional"))
    )
    (net (code "108") (name "Net-(M3-2)") (class "Default")
      (node (ref "H2") (pin "5") (pinfunction "A02_5") (pintype "bidirectional"))
      (node (ref "H2") (pin "6") (pinfunction "A02_6") (pintype "bidirectional"))
      (node (ref "M3") (pin "P$2") (pinfunction "2_P$2") (pintype "bidirectional"))
    )
    (net (code "109") (name "Net-(M4-1)") (class "Default")
      (node (ref "H2") (pin "7") (pinfunction "B02_7") (pintype "bidirectional"))
      (node (ref "H2") (pin "8") (pinfunction "B02_8") (pintype "bidirectional"))
      (node (ref "M4") (pin "P$1") (pinfunction "1_P$1") (pintype "bidirectional"))
    )
    (net (code "110") (name "Net-(M4-2)") (class "Default")
      (node (ref "H2") (pin "11") (pinfunction "B01_11") (pintype "bidirectional"))
      (node (ref "H2") (pin "12") (pinfunction "B01_12") (pintype "bidirectional"))
      (node (ref "M4") (pin "P$2") (pinfunction "2_P$2") (pintype "bidirectional"))
    )
    (net (code "111") (name "Net-(PROT-VDD)") (class "Default")
      (node (ref "C15") (pin "2") (pinfunction "2_2") (pintype "passive"))
      (node (ref "PROT") (pin "5") (pinfunction "VDD_5") (pintype "bidirectional"))
      (node (ref "R44") (pin "2") (pinfunction "2_2") (pintype "passive"))
    )
    (net (code "112") (name "Net-(R21-Pad1)") (class "Default")
      (node (ref "R21") (pin "1") (pinfunction "1_1") (pintype "passive"))
      (node (ref "RED") (pin "C") (pinfunction "C_C") (pintype "passive"))
    )
    (net (code "113") (name "Net-(U$1-1)") (class "Default")
      (node (ref "R36") (pin "2") (pinfunction "2_2") (pintype "passive"))
      (node (ref "U$1") (pin "P$1") (pinfunction "1_P$1") (pintype "bidirectional"))
    )
    (net (code "114") (name "Net-(U$1-2)") (class "Default")
      (node (ref "R37") (pin "2") (pinfunction "2_2") (pintype "passive"))
      (node (ref "U$1") (pin "P$2") (pinfunction "2_P$2") (pintype "bidirectional"))
    )
    (net (code "115") (name "Net-(U$1-3)") (class "Default")
      (node (ref "R38") (pin "2") (pinfunction "2_2") (pintype "passive"))
      (node (ref "U$1") (pin "P$3") (pinfunction "3_P$3") (pintype "bidirectional"))
    )
    (net (code "116") (name "Net-(U$1-4)") (class "Default")
      (node (ref "R39") (pin "2") (pinfunction "2_2") (pintype "passive"))
      (node (ref "U$1") (pin "P$4") (pinfunction "4_P$4") (pintype "bidirectional"))
    )
    (net (code "117") (name "Net-(U$1-5)") (class "Default")
      (node (ref "R40") (pin "2") (pinfunction "2_2") (pintype "passive"))
      (node (ref "U$1") (pin "P$5") (pinfunction "5_P$5") (pintype "bidirectional"))
    )
    (net (code "118") (name "Net-(U$1-6)") (class "Default")
      (node (ref "R41") (pin "2") (pinfunction "2_2") (pintype "passive"))
      (node (ref "U$1") (pin "P$6") (pinfunction "6_P$6") (pintype "bidirectional"))
    )
    (net (code "119") (name "Net-(U$1-7)") (class "Default")
      (node (ref "R42") (pin "2") (pinfunction "2_2") (pintype "passive"))
      (node (ref "U$1") (pin "P$19") (pinfunction "7_P$19") (pintype "bidirectional"))
    )
    (net (code "120") (name "Net-(U$1-8)") (class "Default")
      (node (ref "R43") (pin "2") (pinfunction "2_2") (pintype "passive"))
      (node (ref "U$1") (pin "P$20") (pinfunction "8_P$20") (pintype "bidirectional"))
    )
    (net (code "121") (name "VDC") (class "Default")
      (node (ref "C12") (pin "1") (pinfunction "1_1") (pintype "passive"))
      (node (ref "C7") (pin "1") (pinfunction "1_1") (pintype "passive"))
      (node (ref "CHG") (pin "A") (pinfunction "A_A") (pintype "passive"))
      (node (ref "CHGIC") (pin "2") (pinfunction "VIN_2") (pintype "bidirectional"))
      (node (ref "D3") (pin "A") (pinfunction "A_A") (pintype "passive"))
      (node (ref "JACK") (pin "1") (pinfunction "1_1") (pintype "passive"))
      (node (ref "R1") (pin "1") (pinfunction "1_1") (pintype "passive"))
    )
    (net (code "122") (name "V_BATT") (class "Default")
      (node (ref "6VREG") (pin "9") (pinfunction "VIN_9") (pintype "bidirectional"))
      (node (ref "C11") (pin "+") (pinfunction "+_+") (pintype "passive"))
      (node (ref "C20") (pin "2") (pinfunction "2_2") (pintype "passive"))
      (node (ref "C25") (pin "1") (pinfunction "1_1") (pintype "passive"))
      (node (ref "C26") (pin "1") (pinfunction "1_1") (pintype "passive"))
      (node (ref "CHGIC") (pin "9") (pinfunction "BATT_9") (pintype "bidirectional"))
      (node (ref "D2") (pin "A") (pinfunction "A_A") (pintype "passive"))
      (node (ref "H1") (pin "13") (pinfunction "VM2_13") (pintype "bidirectional"))
      (node (ref "H1") (pin "14") (pinfunction "VM3_14") (pintype "bidirectional"))
      (node (ref "H1") (pin "24") (pinfunction "VM1_24") (pintype "bidirectional"))
      (node (ref "H2") (pin "13") (pinfunction "VM2_13") (pintype "bidirectional"))
      (node (ref "H2") (pin "14") (pinfunction "VM3_14") (pintype "bidirectional"))
      (node (ref "H2") (pin "24") (pinfunction "VM1_24") (pintype "bidirectional"))
      (node (ref "LIPO") (pin "P$1") (pinfunction "1_P$1") (pintype "passive"))
      (node (ref "R19") (pin "1") (pinfunction "1_1") (pintype "passive"))
      (node (ref "R28") (pin "1") (pinfunction "1_1") (pintype "passive"))
      (node (ref "R34") (pin "1") (pinfunction "1_1") (pintype "passive"))
      (node (ref "R4") (pin "1") (pinfunction "1_1") (pintype "passive"))
    )
    (net (code "123") (name "unconnected-(BBB_HEADERS-AIN4-Pad79)") (class "Default")
      (node (ref "BBB_HEADERS") (pin "79") (pinfunction "AIN4_79") (pintype "passive"))
    )
    (net (code "124") (name "unconnected-(BBB_HEADERS-P8_3-Pad3)") (class "Default")
      (node (ref "BBB_HEADERS") (pin "3") (pinfunction "P8_3_3") (pintype "passive"))
    )
    (net (code "125") (name "unconnected-(BBB_HEADERS-P8_4-Pad4)") (class "Default")
      (node (ref "BBB_HEADERS") (pin "4") (pinfunction "P8_4_4") (pintype "passive"))
    )
    (net (code "126") (name "unconnected-(BBB_HEADERS-P8_5-Pad5)") (class "Default")
      (node (ref "BBB_HEADERS") (pin "5") (pinfunction "P8_5_5") (pintype "passive"))
    )
    (net (code "127") (name "unconnected-(BBB_HEADERS-P8_6-Pad6)") (class "Default")
      (node (ref "BBB_HEADERS") (pin "6") (pinfunction "P8_6_6") (pintype "passive"))
    )
    (net (code "128") (name "unconnected-(BBB_HEADERS-P8_20-Pad20)") (class "Default")
      (node (ref "BBB_HEADERS") (pin "20") (pinfunction "P8_20_20") (pintype "passive"))
    )
    (net (code "129") (name "unconnected-(BBB_HEADERS-P8_21-Pad21)") (class "Default")
      (node (ref "BBB_HEADERS") (pin "21") (pinfunction "P8_21_21") (pintype "passive"))
    )
    (net (code "130") (name "unconnected-(BBB_HEADERS-P8_22-Pad22)") (class "Default")
      (node (ref "BBB_HEADERS") (pin "22") (pinfunction "P8_22_22") (pintype "passive"))
    )
    (net (code "131") (name "unconnected-(BBB_HEADERS-P8_23-Pad23)") (class "Default")
      (node (ref "BBB_HEADERS") (pin "23") (pinfunction "P8_23_23") (pintype "passive"))
    )
    (net (code "132") (name "unconnected-(BBB_HEADERS-P8_24-Pad24)") (class "Default")
      (node (ref "BBB_HEADERS") (pin "24") (pinfunction "P8_24_24") (pintype "passive"))
    )
    (net (code "133") (name "unconnected-(BBB_HEADERS-P8_25-Pad25)") (class "Default")
      (node (ref "BBB_HEADERS") (pin "25") (pinfunction "P8_25_25") (pintype "passive"))
    )
    (net (code "134") (name "unconnected-(BBB_HEADERS-P8_31-Pad31)") (class "Default")
      (node (ref "BBB_HEADERS") (pin "31") (pinfunction "P8_31_31") (pintype "passive"))
    )
    (net (code "135") (name "unconnected-(BBB_HEADERS-P8_32-Pad32)") (class "Default")
      (node (ref "BBB_HEADERS") (pin "32") (pinfunction "P8_32_32") (pintype "passive"))
    )
    (net (code "136") (name "unconnected-(CHGIC-ACOK-Pad12)") (class "Default")
      (node (ref "CHGIC") (pin "12") (pinfunction "ACOK_12") (pintype "bidirectional"))
    )
    (net (code "137") (name "unconnected-(CHGIC-CELL-Pad4)") (class "Default")
      (node (ref "CHGIC") (pin "4") (pinfunction "CELL_4") (pintype "bidirectional"))
    )
    (net (code "138") (name "unconnected-(CHGIC-SEL-Pad5)") (class "Default")
      (node (ref "CHGIC") (pin "5") (pinfunction "SEL_5") (pintype "bidirectional"))
    )
    (net (code "139") (name "unconnected-(GPS-Pad1)") (class "Default")
      (node (ref "GPS") (pin "1") (pinfunction "1_1") (pintype "bidirectional"))
    )
    (net (code "140") (name "unconnected-(IMU-AUX_CL-Pad7)") (class "Default")
      (node (ref "IMU") (pin "7") (pinfunction "AUX_CL_7") (pintype "bidirectional"))
    )
    (net (code "141") (name "unconnected-(IMU-AUX_DA-Pad21)") (class "Default")
      (node (ref "IMU") (pin "21") (pinfunction "AUX_DA_21") (pintype "bidirectional"))
    )
    (net (code "142") (name "unconnected-(IMU-FSYNC-Pad11)") (class "Default")
      (node (ref "IMU") (pin "11") (pinfunction "FSYNC_11") (pintype "bidirectional"))
    )
    (net (code "143") (name "unconnected-(IMU-NC-Pad2)") (class "Default")
      (node (ref "IMU") (pin "2") (pinfunction "NC_2") (pintype "bidirectional"))
    )
    (net (code "144") (name "unconnected-(IMU-NC-Pad3)") (class "Default")
      (node (ref "IMU") (pin "3") (pinfunction "NC_3") (pintype "bidirectional"))
    )
    (net (code "145") (name "unconnected-(IMU-NC-Pad4)") (class "Default")
      (node (ref "IMU") (pin "4") (pinfunction "NC_4") (pintype "bidirectional"))
    )
    (net (code "146") (name "unconnected-(IMU-NC-Pad5)") (class "Default")
      (node (ref "IMU") (pin "5") (pinfunction "NC_5") (pintype "bidirectional"))
    )
    (net (code "147") (name "unconnected-(IMU-NC-Pad6)") (class "Default")
      (node (ref "IMU") (pin "6") (pinfunction "NC_6") (pintype "bidirectional"))
    )
    (net (code "148") (name "unconnected-(IMU-NC-Pad14)") (class "Default")
      (node (ref "IMU") (pin "14") (pinfunction "NC_14") (pintype "bidirectional"))
    )
    (net (code "149") (name "unconnected-(IMU-NC-Pad15)") (class "Default")
      (node (ref "IMU") (pin "15") (pinfunction "NC_15") (pintype "bidirectional"))
    )
    (net (code "150") (name "unconnected-(IMU-NC-Pad16)") (class "Default")
      (node (ref "IMU") (pin "16") (pinfunction "NC_16") (pintype "bidirectional"))
    )
    (net (code "151") (name "unconnected-(IMU-NC-Pad17)") (class "Default")
      (node (ref "IMU") (pin "17") (pinfunction "NC_17") (pintype "bidirectional"))
    )
    (net (code "152") (name "unconnected-(IMU-RESV-Pad19)") (class "Default")
      (node (ref "IMU") (pin "19") (pinfunction "RESV_19") (pintype "bidirectional"))
    )
    (net (code "153") (name "unconnected-(PROT-CO-Pad3)") (class "Default")
      (node (ref "PROT") (pin "3") (pinfunction "CO_3") (pintype "bidirectional"))
    )
    (net (code "154") (name "unconnected-(PROT-DP-Pad4)") (class "Default")
      (node (ref "PROT") (pin "4") (pinfunction "DP_4") (pintype "bidirectional"))
    )
  )
)
